# filaSens.net
KiCad netlist of a schematic drawn in EAGLE
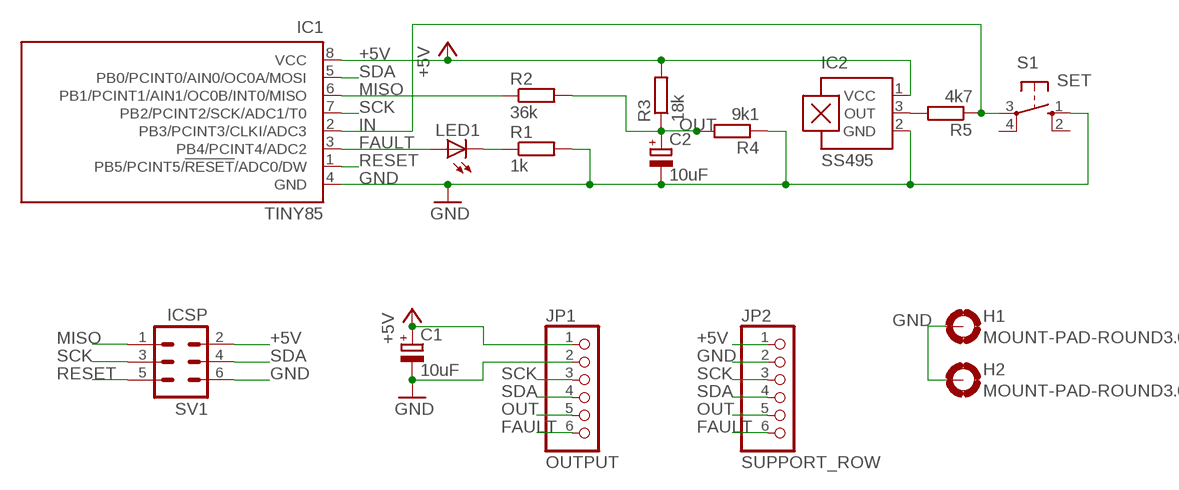
[diagram p0: schematic, sheet 1]

(export (version "E")
  (design (tool "Eeschema 10.0.6"))
  (components
    (comp (ref "C1")
      (value "10uF")
      (footprint "eagle-import:E2,5-5")
      (libsource (lib "eagle-import") (part "CPOL-EUE2.5-5"))
    )
    (comp (ref "C2")
      (value "10uF")
      (footprint "eagle-import:E2,5-5")
      (libsource (lib "eagle-import") (part "CPOL-EUE2.5-5"))
    )
    (comp (ref "H1")
      (value "MOUNT-PAD-ROUND3.0")
      (footprint "eagle-import:3,0-PAD")
      (libsource (lib "eagle-import") (part "MOUNT-PAD-ROUND3.0"))
    )
    (comp (ref "H2")
      (value "MOUNT-PAD-ROUND3.0")
      (footprint "eagle-import:3,0-PAD")
      (libsource (lib "eagle-import") (part "MOUNT-PAD-ROUND3.0"))
    )
    (comp (ref "IC1")
      (value "TINY85")
      (footprint "eagle-import:DIL08")
      (fields (field (name "MPN") "ATTINY13-20PU"))
      (libsource (lib "eagle-import") (part "TINY13PU-20"))
    )
    (comp (ref "IC2")
      (value "SS495")
      (footprint "eagle-import:SIP3-UA")
      (fields (field (name "MF") "ALLEGRO MICROSYSTEMS, INC.") (field (name "MPN") "A1302EUA-T"))
      (libsource (lib "eagle-import") (part "A13?UA02"))
    )
    (comp (ref "JP1")
      (value "OUTPUT")
      (footprint "eagle-import:1X06")
      (libsource (lib "eagle-import") (part "PINHD-1X6"))
    )
    (comp (ref "JP2")
      (value "SUPPORT_ROW")
      (footprint "eagle-import:1X06")
      (libsource (lib "eagle-import") (part "PINHD-1X6"))
    )
    (comp (ref "LED1")
      (value "TLLG4400")
      (footprint "eagle-import:LED3MM")
      (fields (field (name "MF") "VISHAY SEMICONDUCTOR"))
      (libsource (lib "eagle-import") (part "TLLG4400"))
    )
    (comp (ref "R1")
      (value "1k")
      (footprint "eagle-import:0207_10")
      (libsource (lib "eagle-import") (part "R-EU_0207/10"))
    )
    (comp (ref "R2")
      (value "36k")
      (footprint "eagle-import:0207_10")
      (libsource (lib "eagle-import") (part "R-EU_0207/10"))
    )
    (comp (ref "R3")
      (value "18k")
      (footprint "eagle-import:0207_10")
      (libsource (lib "eagle-import") (part "R-EU_0207/10"))
    )
    (comp (ref "R4")
      (value "9k1")
      (footprint "eagle-import:0207_10")
      (libsource (lib "eagle-import") (part "R-EU_0207/10"))
    )
    (comp (ref "R5")
      (value "4k7")
      (footprint "eagle-import:0207_10")
      (libsource (lib "eagle-import") (part "R-EU_0207/10"))
    )
    (comp (ref "S1")
      (value "SET")
      (footprint "eagle-import:B3F-10XX")
      (fields (field (name "MPN") "B3F-1000"))
      (libsource (lib "eagle-import") (part "10-XX"))
    )
    (comp (ref "SV1")
      (value "ICSP")
      (footprint "eagle-import:MA03-2")
      (libsource (lib "eagle-import") (part "MA03-2"))
    )
  )
  (nets
    (net (code "1") (name "+5V") (class "Default")
      (node (ref "C1") (pin "+") (pinfunction "+_+") (pintype "passive"))
      (node (ref "IC1") (pin "8") (pinfunction "VCC_8") (pintype "power_in"))
      (node (ref "IC2") (pin "1") (pinfunction "VCC_1") (pintype "power_in"))
      (node (ref "JP1") (pin "1") (pinfunction "1_1") (pintype "passive"))
      (node (ref "JP2") (pin "1") (pinfunction "1_1") (pintype "passive"))
      (node (ref "R3") (pin "2") (pinfunction "2_2") (pintype "passive"))
      (node (ref "SV1") (pin "2") (pinfunction "2_2") (pintype "passive"))
    )
    (net (code "2") (name "/FAULT") (class "Default")
      (node (ref "IC1") (pin "3") (pinfunction "PB4/PCINT4/ADC2_3") (pintype "bidirectional"))
      (node (ref "JP1") (pin "6") (pinfunction "6_6") (pintype "passive"))
      (node (ref "JP2") (pin "6") (pinfunction "6_6") (pintype "passive"))
      (node (ref "LED1") (pin "A") (pinfunction "A_A") (pintype "passive"))
    )
    (net (code "3") (name "/IN") (class "Default")
      (node (ref "IC1") (pin "2") (pinfunction "PB3/PCINT3/CLKI/ADC3_2") (pintype "bidirectional"))
      (node (ref "R5") (pin "1") (pinfunction "1_1") (pintype "passive"))
      (node (ref "S1") (pin "3") (pinfunction "P_3") (pintype "passive"))
    )
    (net (code "4") (name "/MISO") (class "Default")
      (node (ref "IC1") (pin "6") (pinfunction "PB1/PCINT1/AIN1/OC0B/INT0/MISO_6") (pintype "bidirectional"))
      (node (ref "R2") (pin "1") (pinfunction "1_1") (pintype "passive"))
      (node (ref "SV1") (pin "1") (pinfunction "1_1") (pintype "passive"))
    )
    (net (code "5") (name "/OUT") (class "Default")
      (node (ref "C2") (pin "+") (pinfunction "+_+") (pintype "passive"))
      (node (ref "JP1") (pin "5") (pinfunction "5_5") (pintype "passive"))
      (node (ref "JP2") (pin "5") (pinfunction "5_5") (pintype "passive"))
      (node (ref "R2") (pin "2") (pinfunction "2_2") (pintype "passive"))
      (node (ref "R3") (pin "1") (pinfunction "1_1") (pintype "passive"))
      (node (ref "R4") (pin "2") (pinfunction "2_2") (pintype "passive"))
    )
    (net (code "6") (name "/RESET") (class "Default")
      (node (ref "IC1") (pin "1") (pinfunction "PB5/PCINT5/~{RESET}/ADC0/DW_1") (pintype "bidirectional"))
      (node (ref "SV1") (pin "5") (pinfunction "5_5") (pintype "passive"))
    )
    (net (code "7") (name "/SCK") (class "Default")
      (node (ref "IC1") (pin "7") (pinfunction "PB2/PCINT2/SCK/ADC1/T0_7") (pintype "bidirectional"))
      (node (ref "JP1") (pin "3") (pinfunction "3_3") (pintype "passive"))
      (node (ref "JP2") (pin "3") (pinfunction "3_3") (pintype "passive"))
      (node (ref "SV1") (pin "3") (pinfunction "3_3") (pintype "passive"))
    )
    (net (code "8") (name "/SDA") (class "Default")
      (node (ref "IC1") (pin "5") (pinfunction "PB0/PCINT0/AIN0/OC0A/MOSI_5") (pintype "bidirectional"))
      (node (ref "JP1") (pin "4") (pinfunction "4_4") (pintype "passive"))
      (node (ref "JP2") (pin "4") (pinfunction "4_4") (pintype "passive"))
      (node (ref "SV1") (pin "4") (pinfunction "4_4") (pintype "passive"))
    )
    (net (code "9") (name "GND") (class "Default")
      (node (ref "C1") (pin "-") (pinfunction "-_-") (pintype "passive"))
      (node (ref "C2") (pin "-") (pinfunction "-_-") (pintype "passive"))
      (node (ref "H1") (pin "B3,0") (pinfunction "MOUNT_B3,0") (pintype "passive"))
      (node (ref "H2") (pin "B3,0") (pinfunction "MOUNT_B3,0") (pintype "passive"))
      (node (ref "IC1") (pin "4") (pinfunction "GND_4") (pintype "power_in"))
      (node (ref "IC2") (pin "2") (pinfunction "GND_2") (pintype "power_in"))
      (node (ref "JP1") (pin "2") (pinfunction "2_2") (pintype "passive"))
      (node (ref "JP2") (pin "2") (pinfunction "2_2") (pintype "passive"))
      (node (ref "R1") (pin "2") (pinfunction "2_2") (pintype "passive"))
      (node (ref "R4") (pin "1") (pinfunction "1_1") (pintype "passive"))
      (node (ref "S1") (pin "1") (pinfunction "S_1") (pintype "passive"))
      (node (ref "SV1") (pin "6") (pinfunction "6_6") (pintype "passive"))
    )
    (net (code "10") (name "Net-(IC2-OUT)") (class "Default")
      (node (ref "IC2") (pin "3") (pinfunction "OUT_3") (pintype "output"))
      (node (ref "R5") (pin "2") (pinfunction "2_2") (pintype "passive"))
    )
    (net (code "11") (name "Net-(LED1-C)") (class "Default")
      (node (ref "LED1") (pin "K") (pinfunction "C_K") (pintype "passive"))
      (node (ref "R1") (pin "1") (pinfunction "1_1") (pintype "passive"))
    )
    (net (code "12") (name "unconnected-(S1-P1-Pad4)") (class "Default")
      (node (ref "S1") (pin "4") (pinfunction "P1_4") (pintype "passive"))
    )
    (net (code "13") (name "unconnected-(S1-S1-Pad2)") (class "Default")
      (node (ref "S1") (pin "2") (pinfunction "S1_2") (pintype "passive"))
    )
  )
)
